# Timer.net
KiCad netlist of a schematic drawn in EAGLE
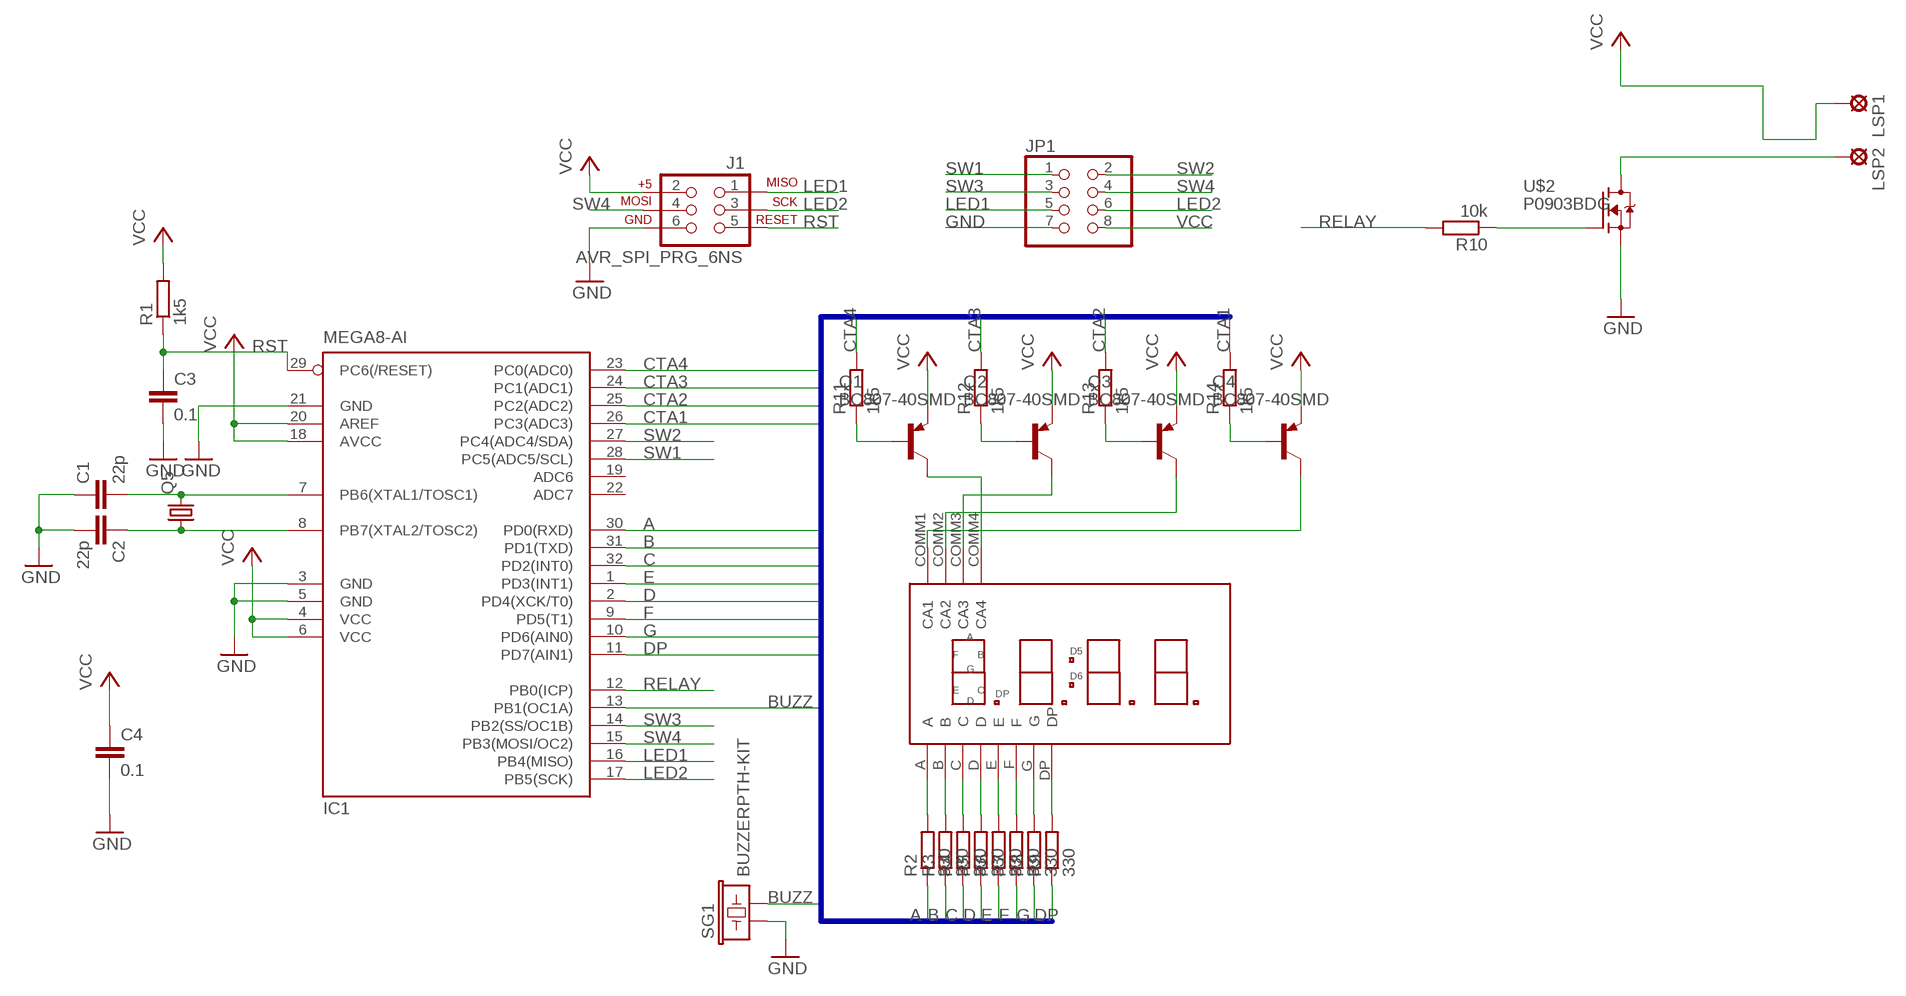
[diagram p0: schematic, sheet 1]

(export (version "E")
  (design (tool "Eeschema 10.0.6"))
  (components
    (comp (ref "C1")
      (value "22p")
      (footprint "eagle-import:C0805")
      (libsource (lib "eagle-import") (part "C-EUC0805"))
    )
    (comp (ref "C2")
      (value "22p")
      (footprint "eagle-import:C0805")
      (libsource (lib "eagle-import") (part "C-EUC0805"))
    )
    (comp (ref "C3")
      (value "0.1")
      (footprint "eagle-import:C0805")
      (libsource (lib "eagle-import") (part "C-EUC0805"))
    )
    (comp (ref "C4")
      (value "0.1")
      (footprint "eagle-import:C0805")
      (libsource (lib "eagle-import") (part "C-EUC0805"))
    )
    (comp (ref "IC1")
      (value "MEGA8-AI")
      (footprint "eagle-import:TQFP32-08")
      (fields (field (name "MPN") "ATMEGA8-16AU"))
      (libsource (lib "eagle-import") (part "MEGA8-AI"))
    )
    (comp (ref "J1")
      (value "AVR_SPI_PRG_6NS")
      (footprint "eagle-import:2X3-NS")
      (libsource (lib "eagle-import") (part "AVR_SPI_PRG_6NS"))
    )
    (comp (ref "JP1")
      (value "PINHD-2X4")
      (footprint "eagle-import:2X04")
      (libsource (lib "eagle-import") (part "PINHD-2X4"))
    )
    (comp (ref "LSP1")
      (value "SE13")
      (footprint "eagle-import:SE13")
      (libsource (lib "eagle-import") (part "SE13"))
    )
    (comp (ref "LSP2")
      (value "SE13")
      (footprint "eagle-import:SE13")
      (libsource (lib "eagle-import") (part "SE13"))
    )
    (comp (ref "Q1")
      (value "BC807-40SMD")
      (footprint "eagle-import:SOT23-BEC")
      (libsource (lib "eagle-import") (part "BC807SMD-40"))
    )
    (comp (ref "Q2")
      (value "BC807-40SMD")
      (footprint "eagle-import:SOT23-BEC")
      (libsource (lib "eagle-import") (part "BC807SMD-40"))
    )
    (comp (ref "Q3")
      (value "BC807-40SMD")
      (footprint "eagle-import:SOT23-BEC")
      (libsource (lib "eagle-import") (part "BC807SMD-40"))
    )
    (comp (ref "Q4")
      (value "BC807-40SMD")
      (footprint "eagle-import:SOT23-BEC")
      (libsource (lib "eagle-import") (part "BC807SMD-40"))
    )
    (comp (ref "Q5")
      (value "CRYSTALHC49UP")
      (footprint "eagle-import:HC49UP")
      (libsource (lib "eagle-import") (part "CRYSTALHC49UP"))
    )
    (comp (ref "R1")
      (value "1k5")
      (footprint "eagle-import:R1206")
      (libsource (lib "eagle-import") (part "R-EU_R1206"))
    )
    (comp (ref "R2")
      (value "330")
      (footprint "eagle-import:R1206")
      (libsource (lib "eagle-import") (part "R-EU_R1206"))
    )
    (comp (ref "R3")
      (value "330")
      (footprint "eagle-import:R1206")
      (libsource (lib "eagle-import") (part "R-EU_R1206"))
    )
    (comp (ref "R4")
      (value "330")
      (footprint "eagle-import:R1206")
      (libsource (lib "eagle-import") (part "R-EU_R1206"))
    )
    (comp (ref "R5")
      (value "330")
      (footprint "eagle-import:R1206")
      (libsource (lib "eagle-import") (part "R-EU_R1206"))
    )
    (comp (ref "R6")
      (value "330")
      (footprint "eagle-import:R1206")
      (libsource (lib "eagle-import") (part "R-EU_R1206"))
    )
    (comp (ref "R7")
      (value "330")
      (footprint "eagle-import:R1206")
      (libsource (lib "eagle-import") (part "R-EU_R1206"))
    )
    (comp (ref "R8")
      (value "330")
      (footprint "eagle-import:R1206")
      (libsource (lib "eagle-import") (part "R-EU_R1206"))
    )
    (comp (ref "R9")
      (value "330")
      (footprint "eagle-import:R1206")
      (libsource (lib "eagle-import") (part "R-EU_R1206"))
    )
    (comp (ref "R10")
      (value "10k")
      (footprint "eagle-import:R1206")
      (libsource (lib "eagle-import") (part "R-EU_R1206"))
    )
    (comp (ref "R11")
      (value "1k5")
      (footprint "eagle-import:R1206")
      (libsource (lib "eagle-import") (part "R-EU_R1206"))
    )
    (comp (ref "R12")
      (value "1k5")
      (footprint "eagle-import:R1206")
      (libsource (lib "eagle-import") (part "R-EU_R1206"))
    )
    (comp (ref "R13")
      (value "1k5")
      (footprint "eagle-import:R1206")
      (libsource (lib "eagle-import") (part "R-EU_R1206"))
    )
    (comp (ref "R14")
      (value "1k5")
      (footprint "eagle-import:R1206")
      (libsource (lib "eagle-import") (part "R-EU_R1206"))
    )
    (comp (ref "SG1")
      (value "BUZZERPTH-KIT")
      (footprint "eagle-import:BUZZER-12MM-KIT")
      (libsource (lib "eagle-import") (part "BUZZERPTH-KIT"))
    )
    (comp (ref "U$1")
      (value "FYG-5564BUG")
      (footprint "eagle-import:FYQ-5643XX")
      (libsource (lib "eagle-import") (part "FYG-5564BUG"))
    )
    (comp (ref "U$2")
      (value "P0903BDG")
      (footprint "eagle-import:TO252")
      (libsource (lib "eagle-import") (part "P0903BDG"))
    )
  )
  (nets
    (net (code "1") (name "/A") (class "Default")
      (node (ref "IC1") (pin "30") (pinfunction "PD0(RXD)_30") (pintype "bidirectional"))
      (node (ref "R2") (pin "1") (pinfunction "1_1") (pintype "passive"))
    )
    (net (code "2") (name "/B") (class "Default")
      (node (ref "IC1") (pin "31") (pinfunction "PD1(TXD)_31") (pintype "bidirectional"))
      (node (ref "R3") (pin "1") (pinfunction "1_1") (pintype "passive"))
    )
    (net (code "3") (name "/BUZZ") (class "Default")
      (node (ref "IC1") (pin "13") (pinfunction "PB1(OC1A)_13") (pintype "bidirectional"))
      (node (ref "SG1") (pin "-") (pinfunction "2_-") (pintype "passive"))
    )
    (net (code "4") (name "/C") (class "Default")
      (node (ref "IC1") (pin "32") (pinfunction "PD2(INT0)_32") (pintype "bidirectional"))
      (node (ref "R4") (pin "1") (pinfunction "1_1") (pintype "passive"))
    )
    (net (code "5") (name "/CTA1") (class "Default")
      (node (ref "IC1") (pin "26") (pinfunction "PC3(ADC3)_26") (pintype "bidirectional"))
      (node (ref "R14") (pin "2") (pinfunction "2_2") (pintype "passive"))
    )
    (net (code "6") (name "/CTA2") (class "Default")
      (node (ref "IC1") (pin "25") (pinfunction "PC2(ADC2)_25") (pintype "bidirectional"))
      (node (ref "R13") (pin "2") (pinfunction "2_2") (pintype "passive"))
    )
    (net (code "7") (name "/CTA3") (class "Default")
      (node (ref "IC1") (pin "24") (pinfunction "PC1(ADC1)_24") (pintype "bidirectional"))
      (node (ref "R12") (pin "2") (pinfunction "2_2") (pintype "passive"))
    )
    (net (code "8") (name "/CTA4") (class "Default")
      (node (ref "IC1") (pin "23") (pinfunction "PC0(ADC0)_23") (pintype "bidirectional"))
      (node (ref "R11") (pin "2") (pinfunction "2_2") (pintype "passive"))
    )
    (net (code "9") (name "/D") (class "Default")
      (node (ref "IC1") (pin "2") (pinfunction "PD4(XCK/T0)_2") (pintype "bidirectional"))
      (node (ref "R5") (pin "1") (pinfunction "1_1") (pintype "passive"))
    )
    (net (code "10") (name "/DP") (class "Default")
      (node (ref "IC1") (pin "11") (pinfunction "PD7(AIN1)_11") (pintype "bidirectional"))
      (node (ref "R9") (pin "1") (pinfunction "1_1") (pintype "passive"))
    )
    (net (code "11") (name "/E") (class "Default")
      (node (ref "IC1") (pin "1") (pinfunction "PD3(INT1)_1") (pintype "bidirectional"))
      (node (ref "R6") (pin "1") (pinfunction "1_1") (pintype "passive"))
    )
    (net (code "12") (name "/F") (class "Default")
      (node (ref "IC1") (pin "9") (pinfunction "PD5(T1)_9") (pintype "bidirectional"))
      (node (ref "R7") (pin "1") (pinfunction "1_1") (pintype "passive"))
    )
    (net (code "13") (name "/G") (class "Default")
      (node (ref "IC1") (pin "10") (pinfunction "PD6(AIN0)_10") (pintype "bidirectional"))
      (node (ref "R8") (pin "1") (pinfunction "1_1") (pintype "passive"))
    )
    (net (code "14") (name "/LED1") (class "Default")
      (node (ref "IC1") (pin "16") (pinfunction "PB4(MISO)_16") (pintype "bidirectional"))
      (node (ref "J1") (pin "1") (pinfunction "1_1") (pintype "passive"))
      (node (ref "JP1") (pin "5") (pinfunction "5_5") (pintype "passive"))
    )
    (net (code "15") (name "/LED2") (class "Default")
      (node (ref "IC1") (pin "17") (pinfunction "PB5(SCK)_17") (pintype "bidirectional"))
      (node (ref "J1") (pin "3") (pinfunction "3_3") (pintype "passive"))
      (node (ref "JP1") (pin "6") (pinfunction "6_6") (pintype "passive"))
    )
    (net (code "16") (name "/RELAY") (class "Default")
      (node (ref "IC1") (pin "12") (pinfunction "PB0(ICP)_12") (pintype "bidirectional"))
      (node (ref "R10") (pin "2") (pinfunction "2_2") (pintype "passive"))
    )
    (net (code "17") (name "/RST") (class "Default")
      (node (ref "C3") (pin "1") (pinfunction "1_1") (pintype "passive"))
      (node (ref "IC1") (pin "29") (pinfunction "PC6(/RESET)_29") (pintype "bidirectional"))
      (node (ref "J1") (pin "5") (pinfunction "5_5") (pintype "passive"))
      (node (ref "R1") (pin "1") (pinfunction "1_1") (pintype "passive"))
    )
    (net (code "18") (name "/SW1") (class "Default")
      (node (ref "IC1") (pin "28") (pinfunction "PC5(ADC5/SCL)_28") (pintype "bidirectional"))
      (node (ref "JP1") (pin "1") (pinfunction "1_1") (pintype "passive"))
    )
    (net (code "19") (name "/SW2") (class "Default")
      (node (ref "IC1") (pin "27") (pinfunction "PC4(ADC4/SDA)_27") (pintype "bidirectional"))
      (node (ref "JP1") (pin "2") (pinfunction "2_2") (pintype "passive"))
    )
    (net (code "20") (name "/SW3") (class "Default")
      (node (ref "IC1") (pin "14") (pinfunction "PB2(SS/OC1B)_14") (pintype "bidirectional"))
      (node (ref "JP1") (pin "3") (pinfunction "3_3") (pintype "passive"))
    )
    (net (code "21") (name "/SW4") (class "Default")
      (node (ref "IC1") (pin "15") (pinfunction "PB3(MOSI/OC2)_15") (pintype "bidirectional"))
      (node (ref "J1") (pin "4") (pinfunction "4_4") (pintype "passive"))
      (node (ref "JP1") (pin "4") (pinfunction "4_4") (pintype "passive"))
    )
    (net (code "22") (name "GND") (class "Default")
      (node (ref "C1") (pin "1") (pinfunction "1_1") (pintype "passive"))
      (node (ref "C2") (pin "2") (pinfunction "2_2") (pintype "passive"))
      (node (ref "C3") (pin "2") (pinfunction "2_2") (pintype "passive"))
      (node (ref "C4") (pin "2") (pinfunction "2_2") (pintype "passive"))
      (node (ref "IC1") (pin "21") (pinfunction "GND_21") (pintype "power_in"))
      (node (ref "IC1") (pin "3") (pinfunction "GND_3") (pintype "power_in"))
      (node (ref "IC1") (pin "5") (pinfunction "GND_5") (pintype "power_in"))
      (node (ref "J1") (pin "6") (pinfunction "6_6") (pintype "passive"))
      (node (ref "JP1") (pin "7") (pinfunction "7_7") (pintype "passive"))
      (node (ref "SG1") (pin "+") (pinfunction "1_+") (pintype "passive"))
      (node (ref "U$2") (pin "3") (pinfunction "S_3") (pintype "passive"))
    )
    (net (code "23") (name "Net-(IC1-PB6(XTAL1{slash}TOSC1))") (class "Default")
      (node (ref "C1") (pin "2") (pinfunction "2_2") (pintype "passive"))
      (node (ref "IC1") (pin "7") (pinfunction "PB6(XTAL1/TOSC1)_7") (pintype "bidirectional"))
      (node (ref "Q5") (pin "2") (pinfunction "2_2") (pintype "passive"))
    )
    (net (code "24") (name "Net-(IC1-PB7(XTAL2{slash}TOSC2))") (class "Default")
      (node (ref "C2") (pin "1") (pinfunction "1_1") (pintype "passive"))
      (node (ref "IC1") (pin "8") (pinfunction "PB7(XTAL2/TOSC2)_8") (pintype "bidirectional"))
      (node (ref "Q5") (pin "1") (pinfunction "1_1") (pintype "passive"))
    )
    (net (code "25") (name "Net-(Q1-PadB)") (class "Default")
      (node (ref "Q1") (pin "B") (pinfunction "B_B") (pintype "passive"))
      (node (ref "R11") (pin "1") (pinfunction "1_1") (pintype "passive"))
    )
    (net (code "26") (name "Net-(Q2-PadB)") (class "Default")
      (node (ref "Q2") (pin "B") (pinfunction "B_B") (pintype "passive"))
      (node (ref "R12") (pin "1") (pinfunction "1_1") (pintype "passive"))
    )
    (net (code "27") (name "Net-(Q3-PadB)") (class "Default")
      (node (ref "Q3") (pin "B") (pinfunction "B_B") (pintype "passive"))
      (node (ref "R13") (pin "1") (pinfunction "1_1") (pintype "passive"))
    )
    (net (code "28") (name "Net-(Q4-PadB)") (class "Default")
      (node (ref "Q4") (pin "B") (pinfunction "B_B") (pintype "passive"))
      (node (ref "R14") (pin "1") (pinfunction "1_1") (pintype "passive"))
    )
    (net (code "29") (name "Net-(R2-Pad2)") (class "Default")
      (node (ref "R2") (pin "2") (pinfunction "2_2") (pintype "passive"))
      (node (ref "U$1") (pin "A") (pinfunction "A_A") (pintype "input"))
    )
    (net (code "30") (name "Net-(R3-Pad2)") (class "Default")
      (node (ref "R3") (pin "2") (pinfunction "2_2") (pintype "passive"))
      (node (ref "U$1") (pin "B") (pinfunction "B_B") (pintype "input"))
    )
    (net (code "31") (name "Net-(R4-Pad2)") (class "Default")
      (node (ref "R4") (pin "2") (pinfunction "2_2") (pintype "passive"))
      (node (ref "U$1") (pin "C") (pinfunction "C_C") (pintype "input"))
    )
    (net (code "32") (name "Net-(R5-Pad2)") (class "Default")
      (node (ref "R5") (pin "2") (pinfunction "2_2") (pintype "passive"))
      (node (ref "U$1") (pin "D") (pinfunction "D_D") (pintype "input"))
    )
    (net (code "33") (name "Net-(R6-Pad2)") (class "Default")
      (node (ref "R6") (pin "2") (pinfunction "2_2") (pintype "passive"))
      (node (ref "U$1") (pin "E") (pinfunction "E_E") (pintype "input"))
    )
    (net (code "34") (name "Net-(R7-Pad2)") (class "Default")
      (node (ref "R7") (pin "2") (pinfunction "2_2") (pintype "passive"))
      (node (ref "U$1") (pin "F") (pinfunction "F_F") (pintype "input"))
    )
    (net (code "35") (name "Net-(R8-Pad2)") (class "Default")
      (node (ref "R8") (pin "2") (pinfunction "2_2") (pintype "passive"))
      (node (ref "U$1") (pin "G") (pinfunction "G_G") (pintype "input"))
    )
    (net (code "36") (name "Net-(R9-Pad2)") (class "Default")
      (node (ref "R9") (pin "2") (pinfunction "2_2") (pintype "passive"))
      (node (ref "U$1") (pin "DP") (pinfunction "DP_DP") (pintype "input"))
    )
    (net (code "37") (name "Net-(U$1-CA1)") (class "Default")
      (node (ref "Q4") (pin "C") (pinfunction "C_C") (pintype "passive"))
      (node (ref "U$1") (pin "COMM1") (pinfunction "CA1_COMM1") (pintype "input"))
    )
    (net (code "38") (name "Net-(U$1-CA2)") (class "Default")
      (node (ref "Q3") (pin "C") (pinfunction "C_C") (pintype "passive"))
      (node (ref "U$1") (pin "COMM2") (pinfunction "CA2_COMM2") (pintype "input"))
    )
    (net (code "39") (name "Net-(U$1-CA3)") (class "Default")
      (node (ref "Q2") (pin "C") (pinfunction "C_C") (pintype "passive"))
      (node (ref "U$1") (pin "COMM3") (pinfunction "CA3_COMM3") (pintype "input"))
    )
    (net (code "40") (name "Net-(U$1-CA4)") (class "Default")
      (node (ref "Q1") (pin "C") (pinfunction "C_C") (pintype "passive"))
      (node (ref "U$1") (pin "COMM4") (pinfunction "CA4_COMM4") (pintype "input"))
    )
    (net (code "41") (name "Net-(U$2-D)") (class "Default")
      (node (ref "LSP2") (pin "MP") (pinfunction "MP_MP") (pintype "passive"))
      (node (ref "U$2") (pin "2") (pinfunction "D_2") (pintype "passive"))
    )
    (net (code "42") (name "Net-(U$2-G)") (class "Default")
      (node (ref "R10") (pin "1") (pinfunction "1_1") (pintype "passive"))
      (node (ref "U$2") (pin "1") (pinfunction "G_1") (pintype "passive"))
    )
    (net (code "43") (name "VCC") (class "Default")
      (node (ref "C4") (pin "1") (pinfunction "1_1") (pintype "passive"))
      (node (ref "IC1") (pin "18") (pinfunction "AVCC_18") (pintype "power_in"))
      (node (ref "IC1") (pin "20") (pinfunction "AREF_20") (pintype "passive"))
      (node (ref "IC1") (pin "4") (pinfunction "VCC_4") (pintype "power_in"))
      (node (ref "IC1") (pin "6") (pinfunction "VCC_6") (pintype "power_in"))
      (node (ref "J1") (pin "2") (pinfunction "2_2") (pintype "passive"))
      (node (ref "JP1") (pin "8") (pinfunction "8_8") (pintype "passive"))
      (node (ref "LSP1") (pin "MP") (pinfunction "MP_MP") (pintype "passive"))
      (node (ref "Q1") (pin "E") (pinfunction "E_E") (pintype "passive"))
      (node (ref "Q2") (pin "E") (pinfunction "E_E") (pintype "passive"))
      (node (ref "Q3") (pin "E") (pinfunction "E_E") (pintype "passive"))
      (node (ref "Q4") (pin "E") (pinfunction "E_E") (pintype "passive"))
      (node (ref "R1") (pin "2") (pinfunction "2_2") (pintype "passive"))
    )
    (net (code "44") (name "unconnected-(IC1-ADC6-Pad19)") (class "Default")
      (node (ref "IC1") (pin "19") (pinfunction "ADC6_19") (pintype "bidirectional"))
    )
    (net (code "45") (name "unconnected-(IC1-ADC7-Pad22)") (class "Default")
      (node (ref "IC1") (pin "22") (pinfunction "ADC7_22") (pintype "bidirectional"))
    )
  )
)
